# ISP_programmer.net
KiCad netlist of a schematic drawn in EAGLE
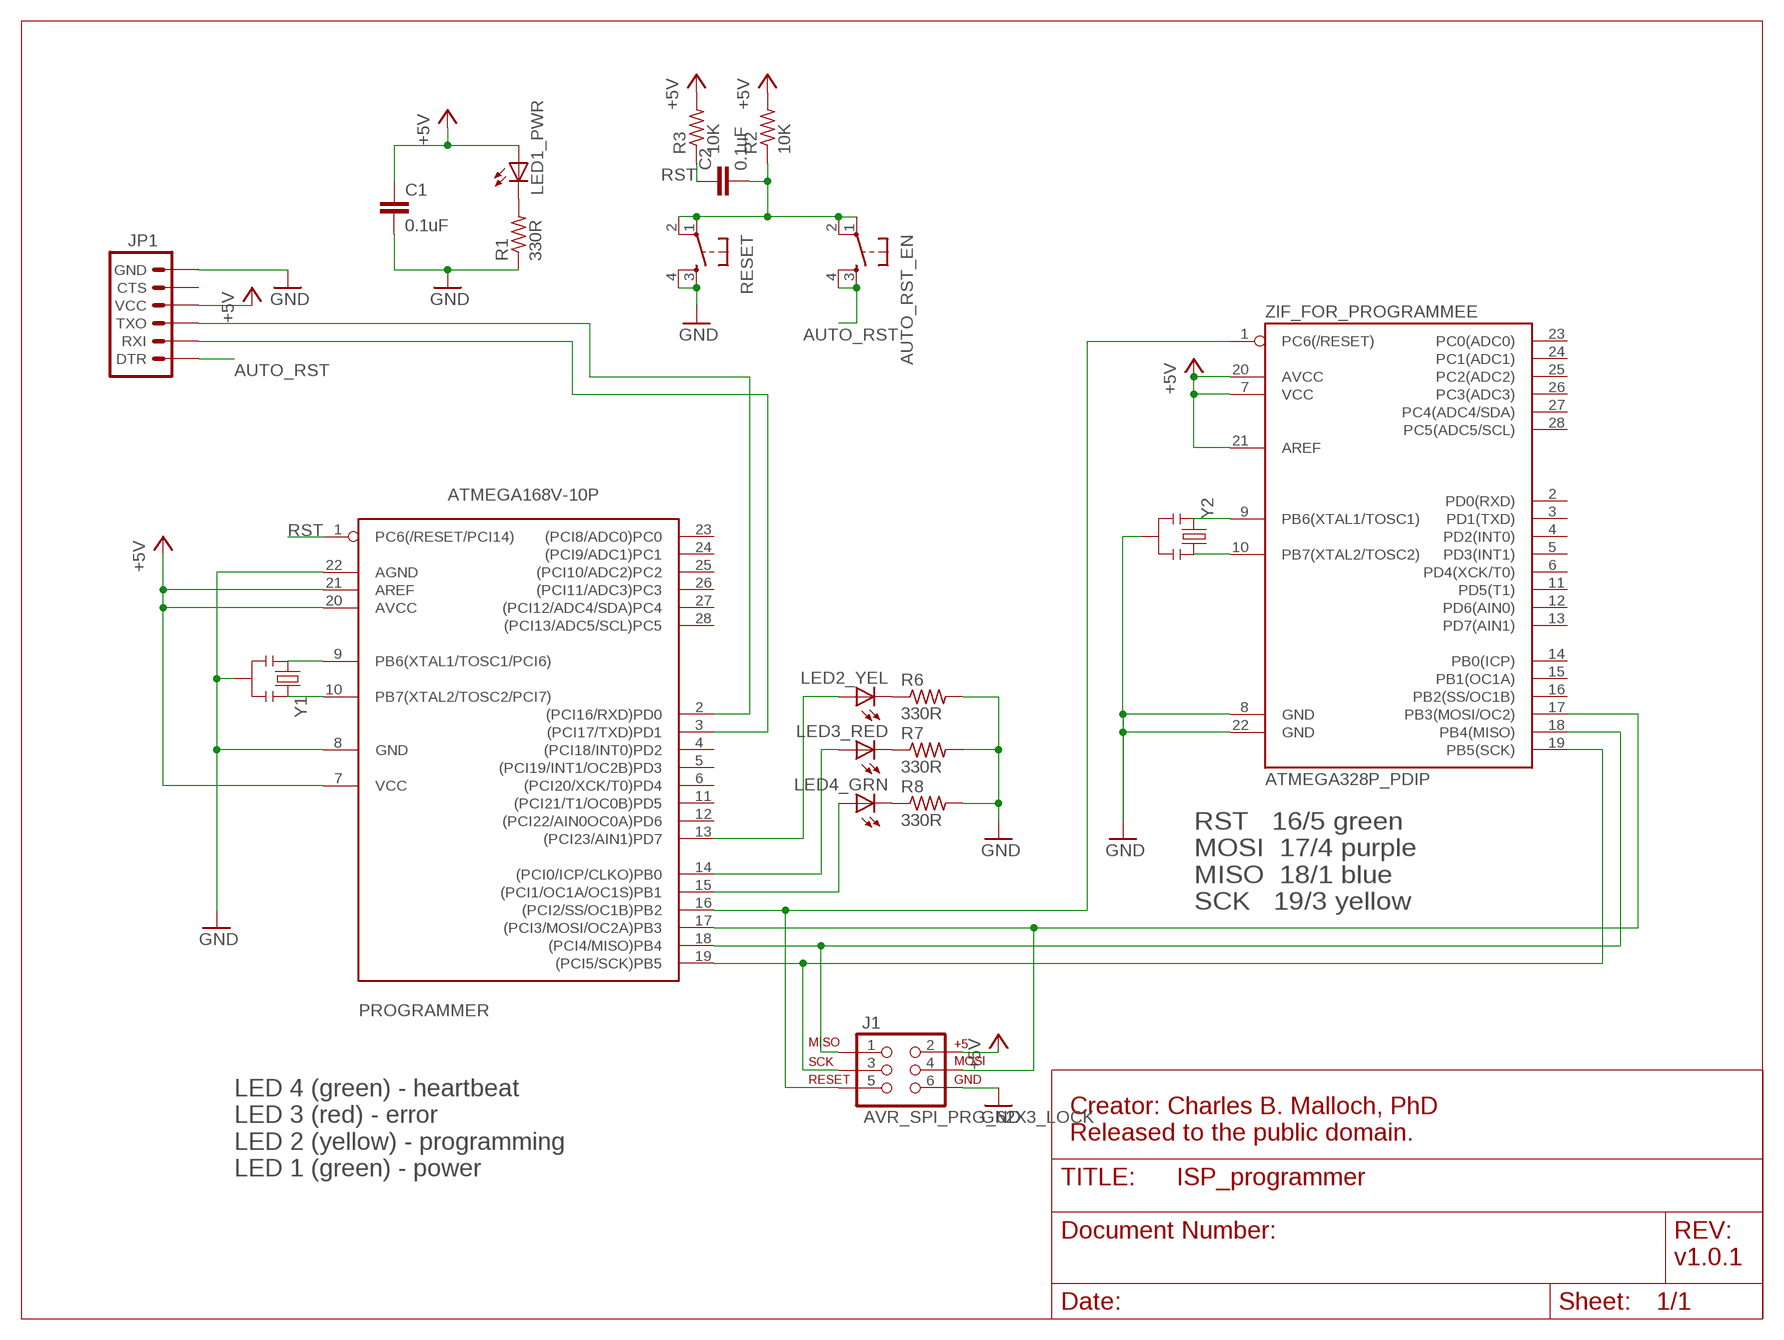
[diagram p0: schematic, sheet 1]

(export (version "E")
  (design (tool "Eeschema 10.0.6"))
  (components
    (comp (ref "AUTO_RST_EN")
      (value "TAC_SWITCHPTH")
      (footprint "eagle-import:TACTILE-PTH")
      (libsource (lib "eagle-import") (part "TAC_SWITCHPTH"))
    )
    (comp (ref "C1")
      (value "0.1uF")
      (footprint "eagle-import:CAP-PTH-SMALLEZ")
      (libsource (lib "eagle-import") (part "CAPEZ"))
    )
    (comp (ref "C2")
      (value "0.1uF")
      (footprint "eagle-import:CAP-PTH-SMALLEZ")
      (libsource (lib "eagle-import") (part "CAPEZ"))
    )
    (comp (ref "J1")
      (value "AVR_SPI_PRG_62X3_LOCK")
      (footprint "eagle-import:2X3_LOCK")
      (libsource (lib "eagle-import") (part "AVR_SPI_PRG_62X3_LOCK"))
    )
    (comp (ref "JP1")
      (value "ARDUINO_SERIAL_PROGRAMLOCK")
      (footprint "eagle-import:1X06_LOCK")
      (libsource (lib "eagle-import") (part "ARDUINO_SERIAL_PROGRAMLOCK"))
    )
    (comp (ref "LED1_PWR")
      (value "LED3MM")
      (footprint "eagle-import:LED3MM")
      (libsource (lib "eagle-import") (part "LED3MM"))
    )
    (comp (ref "LED2_YEL")
      (value "LED3MM")
      (footprint "eagle-import:LED3MM")
      (libsource (lib "eagle-import") (part "LED3MM"))
    )
    (comp (ref "LED3_RED")
      (value "LED3MM")
      (footprint "eagle-import:LED3MM")
      (libsource (lib "eagle-import") (part "LED3MM"))
    )
    (comp (ref "LED4_GRN")
      (value "LED3MM")
      (footprint "eagle-import:LED3MM")
      (libsource (lib "eagle-import") (part "LED3MM"))
    )
    (comp (ref "PROGRAMMER")
      (value "ATMEGA168V-10P")
      (footprint "eagle-import:DIL28-3")
      (libsource (lib "eagle-import") (part "ATMEGA168PV-10"))
    )
    (comp (ref "R1")
      (value "330R")
      (footprint "eagle-import:0204_7")
      (libsource (lib "eagle-import") (part "R-US_0204/7"))
    )
    (comp (ref "R2")
      (value "10K")
      (footprint "eagle-import:0204_7")
      (libsource (lib "eagle-import") (part "R-US_0204/7"))
    )
    (comp (ref "R3")
      (value "10K")
      (footprint "eagle-import:0204_7")
      (libsource (lib "eagle-import") (part "R-US_0204/7"))
    )
    (comp (ref "R6")
      (value "330R")
      (footprint "eagle-import:0204_7")
      (libsource (lib "eagle-import") (part "R-US_0204/7"))
    )
    (comp (ref "R7")
      (value "330R")
      (footprint "eagle-import:0204_7")
      (libsource (lib "eagle-import") (part "R-US_0204/7"))
    )
    (comp (ref "R8")
      (value "330R")
      (footprint "eagle-import:0204_7")
      (libsource (lib "eagle-import") (part "R-US_0204/7"))
    )
    (comp (ref "RESET")
      (value "TAC_SWITCHPTH")
      (footprint "eagle-import:TACTILE-PTH")
      (libsource (lib "eagle-import") (part "TAC_SWITCHPTH"))
    )
    (comp (ref "Y1")
      (value "RESONATORPTH")
      (footprint "eagle-import:RESONATOR-PTH")
      (libsource (lib "eagle-import") (part "RESONATORPTH"))
    )
    (comp (ref "Y2")
      (value "RESONATORPTH")
      (footprint "eagle-import:RESONATOR-PTH")
      (libsource (lib "eagle-import") (part "RESONATORPTH"))
    )
    (comp (ref "ZIF_FOR_PROGRAMMEE")
      (value "ATMEGA328P_PDIP")
      (footprint "eagle-import:DIL28-3")
      (libsource (lib "eagle-import") (part "ATMEGA328P_PDIP"))
    )
  )
  (nets
    (net (code "1") (name "+5V") (class "Default")
      (node (ref "C1") (pin "1") (pinfunction "1_1") (pintype "passive"))
      (node (ref "J1") (pin "2") (pinfunction "2_2") (pintype "passive"))
      (node (ref "JP1") (pin "4") (pinfunction "VCC_4") (pintype "passive"))
      (node (ref "LED1_PWR") (pin "A") (pinfunction "A_A") (pintype "passive"))
      (node (ref "PROGRAMMER") (pin "20") (pinfunction "AVCC_20") (pintype "bidirectional"))
      (node (ref "PROGRAMMER") (pin "21") (pinfunction "AREF_21") (pintype "bidirectional"))
      (node (ref "PROGRAMMER") (pin "7") (pinfunction "VCC_7") (pintype "bidirectional"))
      (node (ref "R2") (pin "2") (pinfunction "2_2") (pintype "passive"))
      (node (ref "R3") (pin "2") (pinfunction "2_2") (pintype "passive"))
      (node (ref "ZIF_FOR_PROGRAMMEE") (pin "20") (pinfunction "AVCC_20") (pintype "bidirectional"))
      (node (ref "ZIF_FOR_PROGRAMMEE") (pin "21") (pinfunction "AREF_21") (pintype "bidirectional"))
      (node (ref "ZIF_FOR_PROGRAMMEE") (pin "7") (pinfunction "VCC_7") (pintype "bidirectional"))
    )
    (net (code "2") (name "/AUTO_RST") (class "Default")
      (node (ref "AUTO_RST_EN") (pin "3") (pinfunction "3_3") (pintype "passive"))
      (node (ref "AUTO_RST_EN") (pin "4") (pinfunction "4_4") (pintype "passive"))
      (node (ref "JP1") (pin "1") (pinfunction "DTR_1") (pintype "passive"))
    )
    (net (code "3") (name "/RST") (class "Default")
      (node (ref "C2") (pin "1") (pinfunction "1_1") (pintype "passive"))
      (node (ref "PROGRAMMER") (pin "1") (pinfunction "PC6(/RESET/PCI14)_1") (pintype "bidirectional"))
      (node (ref "R3") (pin "1") (pinfunction "1_1") (pintype "passive"))
    )
    (net (code "4") (name "GND") (class "Default")
      (node (ref "C1") (pin "2") (pinfunction "2_2") (pintype "passive"))
      (node (ref "J1") (pin "6") (pinfunction "6_6") (pintype "passive"))
      (node (ref "JP1") (pin "6") (pinfunction "GND_6") (pintype "passive"))
      (node (ref "PROGRAMMER") (pin "22") (pinfunction "AGND_22") (pintype "bidirectional"))
      (node (ref "PROGRAMMER") (pin "8") (pinfunction "GND_8") (pintype "bidirectional"))
      (node (ref "R1") (pin "1") (pinfunction "1_1") (pintype "passive"))
      (node (ref "R6") (pin "2") (pinfunction "2_2") (pintype "passive"))
      (node (ref "R7") (pin "2") (pinfunction "2_2") (pintype "passive"))
      (node (ref "R8") (pin "2") (pinfunction "2_2") (pintype "passive"))
      (node (ref "RESET") (pin "3") (pinfunction "3_3") (pintype "passive"))
      (node (ref "RESET") (pin "4") (pinfunction "4_4") (pintype "passive"))
      (node (ref "Y1") (pin "2") (pinfunction "2_2") (pintype "passive"))
      (node (ref "Y2") (pin "2") (pinfunction "2_2") (pintype "passive"))
      (node (ref "ZIF_FOR_PROGRAMMEE") (pin "22") (pinfunction "GND_22") (pintype "bidirectional"))
      (node (ref "ZIF_FOR_PROGRAMMEE") (pin "8") (pinfunction "GND_8") (pintype "bidirectional"))
    )
    (net (code "5") (name "Net-(AUTO_RST_EN-Pad1)") (class "Default")
      (node (ref "AUTO_RST_EN") (pin "1") (pinfunction "1_1") (pintype "passive"))
      (node (ref "AUTO_RST_EN") (pin "2") (pinfunction "2_2") (pintype "passive"))
      (node (ref "C2") (pin "2") (pinfunction "2_2") (pintype "passive"))
      (node (ref "R2") (pin "1") (pinfunction "1_1") (pintype "passive"))
      (node (ref "RESET") (pin "1") (pinfunction "1_1") (pintype "passive"))
      (node (ref "RESET") (pin "2") (pinfunction "2_2") (pintype "passive"))
    )
    (net (code "6") (name "Net-(JP1-RXI)") (class "Default")
      (node (ref "JP1") (pin "2") (pinfunction "RXI_2") (pintype "passive"))
      (node (ref "PROGRAMMER") (pin "3") (pinfunction "(PCI17/TXD)PD1_3") (pintype "bidirectional"))
    )
    (net (code "7") (name "Net-(JP1-TXO)") (class "Default")
      (node (ref "JP1") (pin "3") (pinfunction "TXO_3") (pintype "passive"))
      (node (ref "PROGRAMMER") (pin "2") (pinfunction "(PCI16/RXD)PD0_2") (pintype "bidirectional"))
    )
    (net (code "8") (name "Net-(LED1_PWR-C)") (class "Default")
      (node (ref "LED1_PWR") (pin "K") (pinfunction "C_K") (pintype "passive"))
      (node (ref "R1") (pin "2") (pinfunction "2_2") (pintype "passive"))
    )
    (net (code "9") (name "Net-(LED2_YEL-C)") (class "Default")
      (node (ref "LED2_YEL") (pin "K") (pinfunction "C_K") (pintype "passive"))
      (node (ref "R6") (pin "1") (pinfunction "1_1") (pintype "passive"))
    )
    (net (code "10") (name "Net-(LED3_RED-C)") (class "Default")
      (node (ref "LED3_RED") (pin "K") (pinfunction "C_K") (pintype "passive"))
      (node (ref "R7") (pin "1") (pinfunction "1_1") (pintype "passive"))
    )
    (net (code "11") (name "Net-(LED4_GRN-C)") (class "Default")
      (node (ref "LED4_GRN") (pin "K") (pinfunction "C_K") (pintype "passive"))
      (node (ref "R8") (pin "1") (pinfunction "1_1") (pintype "passive"))
    )
    (net (code "12") (name "Net-(PROGRAMMER-(PCI0{slash}ICP{slash}CLKO)PB0)") (class "Default")
      (node (ref "LED3_RED") (pin "A") (pinfunction "A_A") (pintype "passive"))
      (node (ref "PROGRAMMER") (pin "14") (pinfunction "(PCI0/ICP/CLKO)PB0_14") (pintype "bidirectional"))
    )
    (net (code "13") (name "Net-(PROGRAMMER-(PCI1{slash}OC1A{slash}OC1S)PB1)") (class "Default")
      (node (ref "LED4_GRN") (pin "A") (pinfunction "A_A") (pintype "passive"))
      (node (ref "PROGRAMMER") (pin "15") (pinfunction "(PCI1/OC1A/OC1S)PB1_15") (pintype "bidirectional"))
    )
    (net (code "14") (name "Net-(PROGRAMMER-(PCI2{slash}SS{slash}OC1B)PB2)") (class "Default")
      (node (ref "J1") (pin "5") (pinfunction "5_5") (pintype "passive"))
      (node (ref "PROGRAMMER") (pin "16") (pinfunction "(PCI2/SS/OC1B)PB2_16") (pintype "bidirectional"))
      (node (ref "ZIF_FOR_PROGRAMMEE") (pin "1") (pinfunction "PC6(/RESET)_1") (pintype "bidirectional"))
    )
    (net (code "15") (name "Net-(PROGRAMMER-(PCI3{slash}MOSI{slash}OC2A)PB3)") (class "Default")
      (node (ref "J1") (pin "4") (pinfunction "4_4") (pintype "passive"))
      (node (ref "PROGRAMMER") (pin "17") (pinfunction "(PCI3/MOSI/OC2A)PB3_17") (pintype "bidirectional"))
      (node (ref "ZIF_FOR_PROGRAMMEE") (pin "17") (pinfunction "PB3(MOSI/OC2)_17") (pintype "bidirectional"))
    )
    (net (code "16") (name "Net-(PROGRAMMER-(PCI4{slash}MISO)PB4)") (class "Default")
      (node (ref "J1") (pin "1") (pinfunction "1_1") (pintype "passive"))
      (node (ref "PROGRAMMER") (pin "18") (pinfunction "(PCI4/MISO)PB4_18") (pintype "bidirectional"))
      (node (ref "ZIF_FOR_PROGRAMMEE") (pin "18") (pinfunction "PB4(MISO)_18") (pintype "bidirectional"))
    )
    (net (code "17") (name "Net-(PROGRAMMER-(PCI5{slash}SCK)PB5)") (class "Default")
      (node (ref "J1") (pin "3") (pinfunction "3_3") (pintype "passive"))
      (node (ref "PROGRAMMER") (pin "19") (pinfunction "(PCI5/SCK)PB5_19") (pintype "bidirectional"))
      (node (ref "ZIF_FOR_PROGRAMMEE") (pin "19") (pinfunction "PB5(SCK)_19") (pintype "bidirectional"))
    )
    (net (code "18") (name "Net-(PROGRAMMER-(PCI23{slash}AIN1)PD7)") (class "Default")
      (node (ref "LED2_YEL") (pin "A") (pinfunction "A_A") (pintype "passive"))
      (node (ref "PROGRAMMER") (pin "13") (pinfunction "(PCI23/AIN1)PD7_13") (pintype "bidirectional"))
    )
    (net (code "19") (name "Net-(PROGRAMMER-PB6(XTAL1{slash}TOSC1{slash}PCI6))") (class "Default")
      (node (ref "PROGRAMMER") (pin "9") (pinfunction "PB6(XTAL1/TOSC1/PCI6)_9") (pintype "bidirectional"))
      (node (ref "Y1") (pin "1") (pinfunction "1_1") (pintype "passive"))
    )
    (net (code "20") (name "Net-(PROGRAMMER-PB7(XTAL2{slash}TOSC2{slash}PCI7))") (class "Default")
      (node (ref "PROGRAMMER") (pin "10") (pinfunction "PB7(XTAL2/TOSC2/PCI7)_10") (pintype "bidirectional"))
      (node (ref "Y1") (pin "3") (pinfunction "3_3") (pintype "passive"))
    )
    (net (code "21") (name "Net-(ZIF_FOR_PROGRAMMEE-PB6(XTAL1{slash}TOSC1))") (class "Default")
      (node (ref "Y2") (pin "3") (pinfunction "3_3") (pintype "passive"))
      (node (ref "ZIF_FOR_PROGRAMMEE") (pin "9") (pinfunction "PB6(XTAL1/TOSC1)_9") (pintype "bidirectional"))
    )
    (net (code "22") (name "Net-(ZIF_FOR_PROGRAMMEE-PB7(XTAL2{slash}TOSC2))") (class "Default")
      (node (ref "Y2") (pin "1") (pinfunction "1_1") (pintype "passive"))
      (node (ref "ZIF_FOR_PROGRAMMEE") (pin "10") (pinfunction "PB7(XTAL2/TOSC2)_10") (pintype "bidirectional"))
    )
    (net (code "23") (name "unconnected-(JP1-CTS-Pad5)") (class "Default")
      (node (ref "JP1") (pin "5") (pinfunction "CTS_5") (pintype "passive"))
    )
    (net (code "24") (name "unconnected-(PROGRAMMER-(PCI8{slash}ADC0)PC0-Pad23)") (class "Default")
      (node (ref "PROGRAMMER") (pin "23") (pinfunction "(PCI8/ADC0)PC0_23") (pintype "bidirectional"))
    )
    (net (code "25") (name "unconnected-(PROGRAMMER-(PCI9{slash}ADC1)PC1-Pad24)") (class "Default")
      (node (ref "PROGRAMMER") (pin "24") (pinfunction "(PCI9/ADC1)PC1_24") (pintype "bidirectional"))
    )
    (net (code "26") (name "unconnected-(PROGRAMMER-(PCI10{slash}ADC2)PC2-Pad25)") (class "Default")
      (node (ref "PROGRAMMER") (pin "25") (pinfunction "(PCI10/ADC2)PC2_25") (pintype "bidirectional"))
    )
    (net (code "27") (name "unconnected-(PROGRAMMER-(PCI11{slash}ADC3)PC3-Pad26)") (class "Default")
      (node (ref "PROGRAMMER") (pin "26") (pinfunction "(PCI11/ADC3)PC3_26") (pintype "bidirectional"))
    )
    (net (code "28") (name "unconnected-(PROGRAMMER-(PCI12{slash}ADC4{slash}SDA)PC4-Pad27)") (class "Default")
      (node (ref "PROGRAMMER") (pin "27") (pinfunction "(PCI12/ADC4/SDA)PC4_27") (pintype "bidirectional"))
    )
    (net (code "29") (name "unconnected-(PROGRAMMER-(PCI13{slash}ADC5{slash}SCL)PC5-Pad28)") (class "Default")
      (node (ref "PROGRAMMER") (pin "28") (pinfunction "(PCI13/ADC5/SCL)PC5_28") (pintype "bidirectional"))
    )
    (net (code "30") (name "unconnected-(PROGRAMMER-(PCI18{slash}INT0)PD2-Pad4)") (class "Default")
      (node (ref "PROGRAMMER") (pin "4") (pinfunction "(PCI18/INT0)PD2_4") (pintype "bidirectional"))
    )
    (net (code "31") (name "unconnected-(PROGRAMMER-(PCI19{slash}INT1{slash}OC2B)PD3-Pad5)") (class "Default")
      (node (ref "PROGRAMMER") (pin "5") (pinfunction "(PCI19/INT1/OC2B)PD3_5") (pintype "bidirectional"))
    )
    (net (code "32") (name "unconnected-(PROGRAMMER-(PCI20{slash}XCK{slash}T0)PD4-Pad6)") (class "Default")
      (node (ref "PROGRAMMER") (pin "6") (pinfunction "(PCI20/XCK/T0)PD4_6") (pintype "bidirectional"))
    )
    (net (code "33") (name "unconnected-(PROGRAMMER-(PCI21{slash}T1{slash}OC0B)PD5-Pad11)") (class "Default")
      (node (ref "PROGRAMMER") (pin "11") (pinfunction "(PCI21/T1/OC0B)PD5_11") (pintype "bidirectional"))
    )
    (net (code "34") (name "unconnected-(PROGRAMMER-(PCI22{slash}AIN0OC0A)PD6-Pad12)") (class "Default")
      (node (ref "PROGRAMMER") (pin "12") (pinfunction "(PCI22/AIN0OC0A)PD6_12") (pintype "bidirectional"))
    )
    (net (code "35") (name "unconnected-(ZIF_FOR_PROGRAMMEE-PB0(ICP)-Pad14)") (class "Default")
      (node (ref "ZIF_FOR_PROGRAMMEE") (pin "14") (pinfunction "PB0(ICP)_14") (pintype "bidirectional"))
    )
    (net (code "36") (name "unconnected-(ZIF_FOR_PROGRAMMEE-PB1(OC1A)-Pad15)") (class "Default")
      (node (ref "ZIF_FOR_PROGRAMMEE") (pin "15") (pinfunction "PB1(OC1A)_15") (pintype "bidirectional"))
    )
    (net (code "37") (name "unconnected-(ZIF_FOR_PROGRAMMEE-PB2(SS{slash}OC1B)-Pad16)") (class "Default")
      (node (ref "ZIF_FOR_PROGRAMMEE") (pin "16") (pinfunction "PB2(SS/OC1B)_16") (pintype "bidirectional"))
    )
    (net (code "38") (name "unconnected-(ZIF_FOR_PROGRAMMEE-PC0(ADC0)-Pad23)") (class "Default")
      (node (ref "ZIF_FOR_PROGRAMMEE") (pin "23") (pinfunction "PC0(ADC0)_23") (pintype "bidirectional"))
    )
    (net (code "39") (name "unconnected-(ZIF_FOR_PROGRAMMEE-PC1(ADC1)-Pad24)") (class "Default")
      (node (ref "ZIF_FOR_PROGRAMMEE") (pin "24") (pinfunction "PC1(ADC1)_24") (pintype "bidirectional"))
    )
    (net (code "40") (name "unconnected-(ZIF_FOR_PROGRAMMEE-PC2(ADC2)-Pad25)") (class "Default")
      (node (ref "ZIF_FOR_PROGRAMMEE") (pin "25") (pinfunction "PC2(ADC2)_25") (pintype "bidirectional"))
    )
    (net (code "41") (name "unconnected-(ZIF_FOR_PROGRAMMEE-PC3(ADC3)-Pad26)") (class "Default")
      (node (ref "ZIF_FOR_PROGRAMMEE") (pin "26") (pinfunction "PC3(ADC3)_26") (pintype "bidirectional"))
    )
    (net (code "42") (name "unconnected-(ZIF_FOR_PROGRAMMEE-PC4(ADC4{slash}SDA)-Pad27)") (class "Default")
      (node (ref "ZIF_FOR_PROGRAMMEE") (pin "27") (pinfunction "PC4(ADC4/SDA)_27") (pintype "bidirectional"))
    )
    (net (code "43") (name "unconnected-(ZIF_FOR_PROGRAMMEE-PC5(ADC5{slash}SCL)-Pad28)") (class "Default")
      (node (ref "ZIF_FOR_PROGRAMMEE") (pin "28") (pinfunction "PC5(ADC5/SCL)_28") (pintype "bidirectional"))
    )
    (net (code "44") (name "unconnected-(ZIF_FOR_PROGRAMMEE-PD0(RXD)-Pad2)") (class "Default")
      (node (ref "ZIF_FOR_PROGRAMMEE") (pin "2") (pinfunction "PD0(RXD)_2") (pintype "bidirectional"))
    )
    (net (code "45") (name "unconnected-(ZIF_FOR_PROGRAMMEE-PD1(TXD)-Pad3)") (class "Default")
      (node (ref "ZIF_FOR_PROGRAMMEE") (pin "3") (pinfunction "PD1(TXD)_3") (pintype "bidirectional"))
    )
    (net (code "46") (name "unconnected-(ZIF_FOR_PROGRAMMEE-PD2(INT0)-Pad4)") (class "Default")
      (node (ref "ZIF_FOR_PROGRAMMEE") (pin "4") (pinfunction "PD2(INT0)_4") (pintype "bidirectional"))
    )
    (net (code "47") (name "unconnected-(ZIF_FOR_PROGRAMMEE-PD3(INT1)-Pad5)") (class "Default")
      (node (ref "ZIF_FOR_PROGRAMMEE") (pin "5") (pinfunction "PD3(INT1)_5") (pintype "bidirectional"))
    )
    (net (code "48") (name "unconnected-(ZIF_FOR_PROGRAMMEE-PD4(XCK{slash}T0)-Pad6)") (class "Default")
      (node (ref "ZIF_FOR_PROGRAMMEE") (pin "6") (pinfunction "PD4(XCK/T0)_6") (pintype "bidirectional"))
    )
    (net (code "49") (name "unconnected-(ZIF_FOR_PROGRAMMEE-PD5(T1)-Pad11)") (class "Default")
      (node (ref "ZIF_FOR_PROGRAMMEE") (pin "11") (pinfunction "PD5(T1)_11") (pintype "bidirectional"))
    )
    (net (code "50") (name "unconnected-(ZIF_FOR_PROGRAMMEE-PD6(AIN0)-Pad12)") (class "Default")
      (node (ref "ZIF_FOR_PROGRAMMEE") (pin "12") (pinfunction "PD6(AIN0)_12") (pintype "bidirectional"))
    )
    (net (code "51") (name "unconnected-(ZIF_FOR_PROGRAMMEE-PD7(AIN1)-Pad13)") (class "Default")
      (node (ref "ZIF_FOR_PROGRAMMEE") (pin "13") (pinfunction "PD7(AIN1)_13") (pintype "bidirectional"))
    )
  )
)
